# ICSP-Breadboard-Header.net
KiCad netlist of a schematic drawn in EAGLE
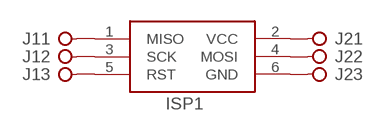
[diagram p0: schematic, sheet 1]

(export (version "E")
  (design (tool "Eeschema 10.0.6"))
  (components
    (comp (ref "ISP1")
      (value "ICSP-HEADER-6")
      (footprint "eagle-import:ICSP-HEADER")
      (libsource (lib "eagle-import") (part "ICSP-HEADER-6"))
    )
    (comp (ref "J1")
      (value "PINHD-1X3")
      (footprint "eagle-import:1X03")
      (libsource (lib "eagle-import") (part "PINHD-1X3"))
    )
    (comp (ref "J2")
      (value "PINHD-1X3")
      (footprint "eagle-import:1X03")
      (libsource (lib "eagle-import") (part "PINHD-1X3"))
    )
  )
  (nets
    (net (code "1") (name "Net-(ISP1-GND)") (class "Default")
      (node (ref "ISP1") (pin "6") (pinfunction "GND_6") (pintype "power_in"))
      (node (ref "J2") (pin "3") (pinfunction "KL_3") (pintype "passive"))
    )
    (net (code "2") (name "Net-(ISP1-MISO)") (class "Default")
      (node (ref "ISP1") (pin "1") (pinfunction "MISO_1") (pintype "input"))
      (node (ref "J1") (pin "1") (pinfunction "KL_1") (pintype "passive"))
    )
    (net (code "3") (name "Net-(ISP1-MOSI)") (class "Default")
      (node (ref "ISP1") (pin "4") (pinfunction "MOSI_4") (pintype "output"))
      (node (ref "J2") (pin "2") (pinfunction "KL_2") (pintype "passive"))
    )
    (net (code "4") (name "Net-(ISP1-RST)") (class "Default")
      (node (ref "ISP1") (pin "5") (pinfunction "RST_5") (pintype "output"))
      (node (ref "J1") (pin "3") (pinfunction "KL_3") (pintype "passive"))
    )
    (net (code "5") (name "Net-(ISP1-SCK)") (class "Default")
      (node (ref "ISP1") (pin "3") (pinfunction "SCK_3") (pintype "output"))
      (node (ref "J1") (pin "2") (pinfunction "KL_2") (pintype "passive"))
    )
    (net (code "6") (name "Net-(ISP1-VCC)") (class "Default")
      (node (ref "ISP1") (pin "2") (pinfunction "VCC_2") (pintype "power_in"))
      (node (ref "J2") (pin "1") (pinfunction "KL_1") (pintype "passive"))
    )
  )
)
